# 011.net
KiCad netlist of a schematic drawn in EAGLE
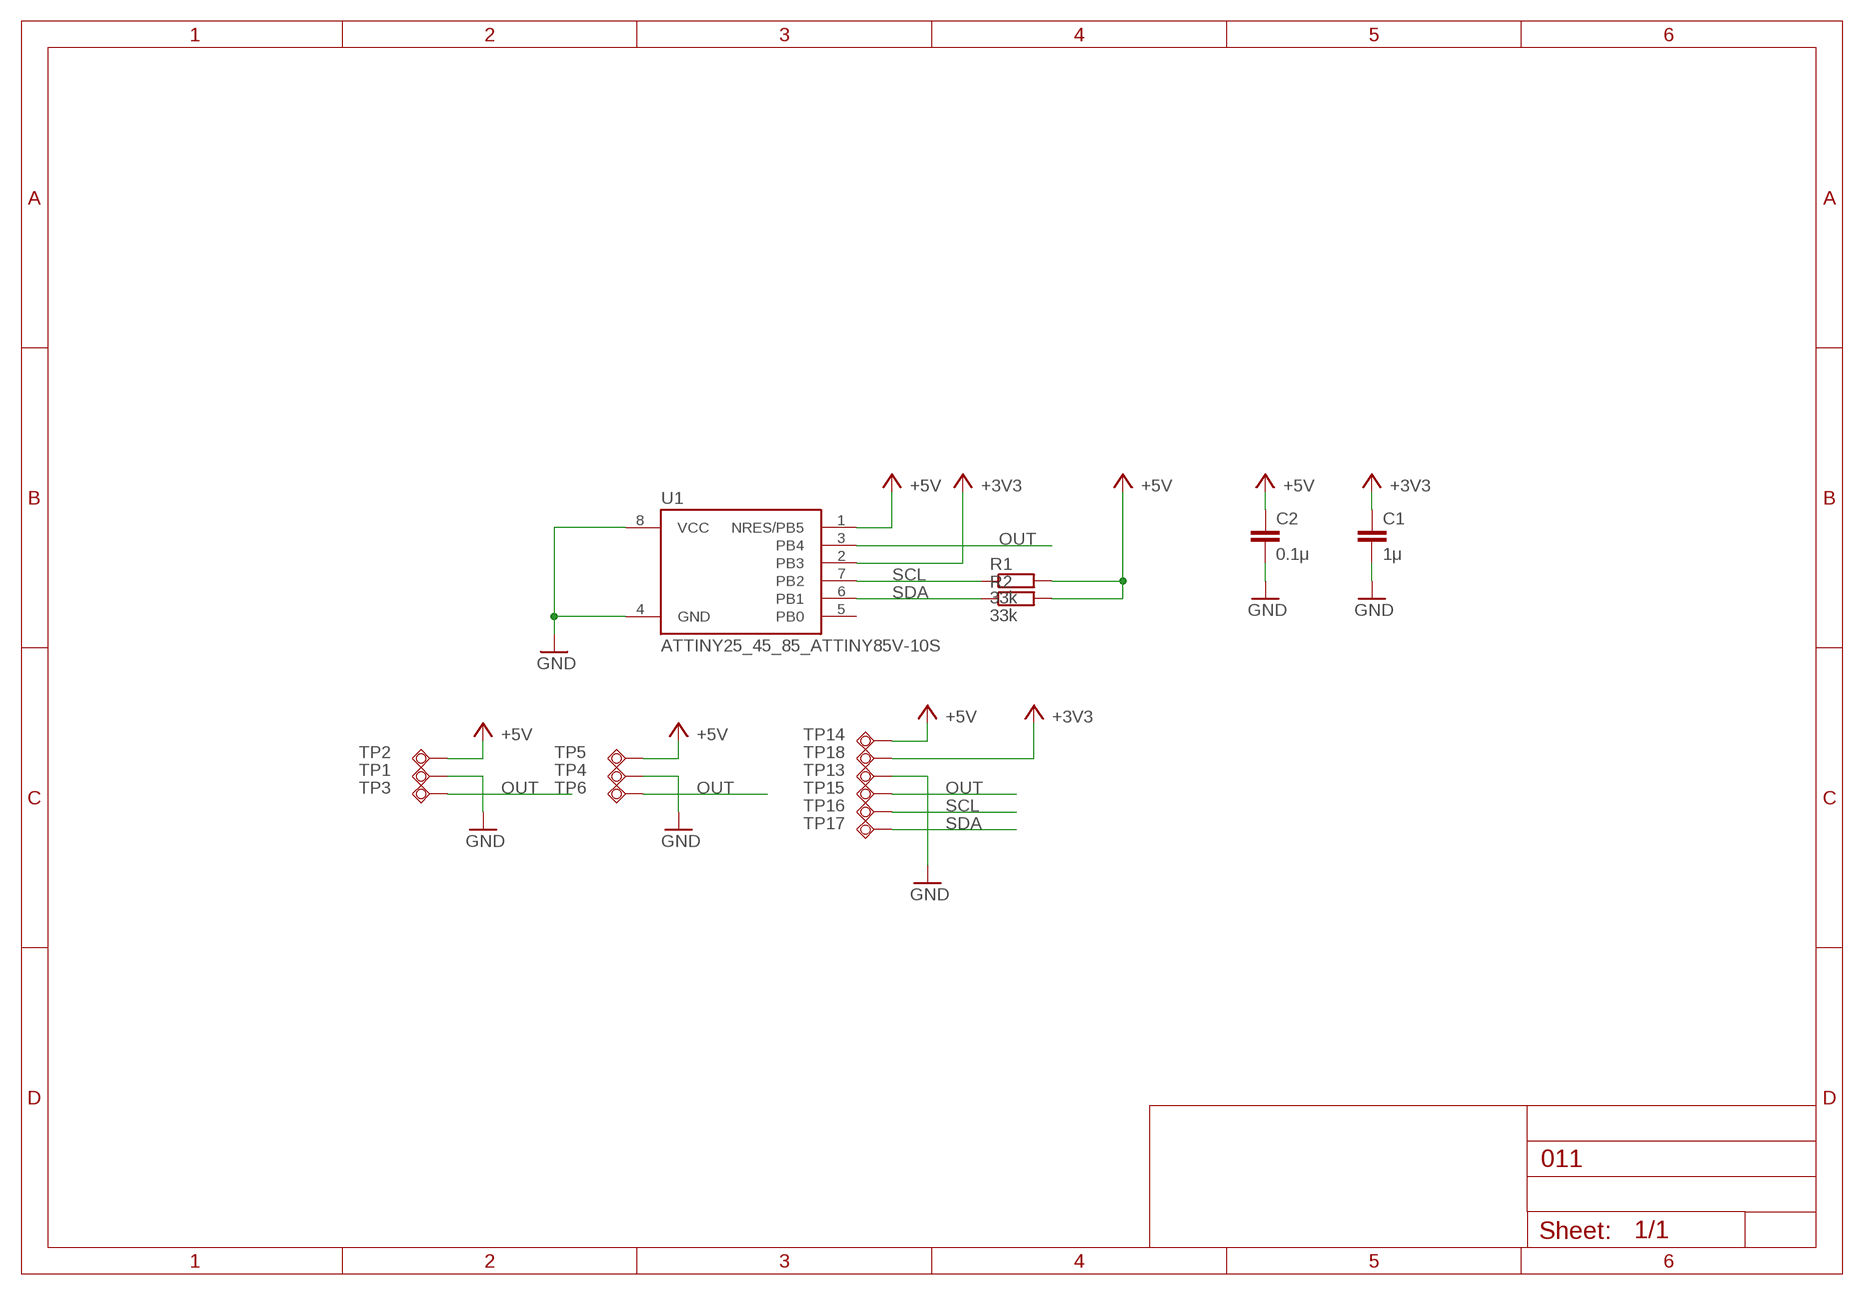
[diagram p0: schematic, sheet 1]

(export (version "E")
  (design (tool "Eeschema 10.0.6"))
  (components
    (comp (ref "C1")
      (value "1μ")
      (footprint "eagle-import:C0603")
      (libsource (lib "eagle-import") (part "C-EUC0603"))
    )
    (comp (ref "C2")
      (value "0.1μ")
      (footprint "eagle-import:C0603")
      (libsource (lib "eagle-import") (part "C-EUC0603"))
    )
    (comp (ref "R1")
      (value "33k")
      (footprint "eagle-import:R0603")
      (libsource (lib "eagle-import") (part "R-EU_R0603"))
    )
    (comp (ref "R2")
      (value "33k")
      (footprint "eagle-import:R0603")
      (libsource (lib "eagle-import") (part "R-EU_R0603"))
    )
    (comp (ref "TP1")
      (value "TPSQTP11R")
      (footprint "eagle-import:TP11R")
      (libsource (lib "eagle-import") (part "TPSQTP11R"))
    )
    (comp (ref "TP2")
      (value "TPSQTP11SQ")
      (footprint "eagle-import:TP11SQ")
      (libsource (lib "eagle-import") (part "TPSQTP11SQ"))
    )
    (comp (ref "TP3")
      (value "TPSQTP11R")
      (footprint "eagle-import:TP11R")
      (libsource (lib "eagle-import") (part "TPSQTP11R"))
    )
    (comp (ref "TP4")
      (value "TPSQTP11R")
      (footprint "eagle-import:TP11R")
      (libsource (lib "eagle-import") (part "TPSQTP11R"))
    )
    (comp (ref "TP5")
      (value "TPSQTP11SQ")
      (footprint "eagle-import:TP11SQ")
      (libsource (lib "eagle-import") (part "TPSQTP11SQ"))
    )
    (comp (ref "TP6")
      (value "TPSQTP11R")
      (footprint "eagle-import:TP11R")
      (libsource (lib "eagle-import") (part "TPSQTP11R"))
    )
    (comp (ref "TP13")
      (value "TPSQTP11R")
      (footprint "eagle-import:TP11R")
      (libsource (lib "eagle-import") (part "TPSQTP11R"))
    )
    (comp (ref "TP14")
      (value "TPSQTP11SQ")
      (footprint "eagle-import:TP11SQ")
      (libsource (lib "eagle-import") (part "TPSQTP11SQ"))
    )
    (comp (ref "TP15")
      (value "TPSQTP11R")
      (footprint "eagle-import:TP11R")
      (libsource (lib "eagle-import") (part "TPSQTP11R"))
    )
    (comp (ref "TP16")
      (value "TPSQTP11R")
      (footprint "eagle-import:TP11R")
      (libsource (lib "eagle-import") (part "TPSQTP11R"))
    )
    (comp (ref "TP17")
      (value "TPSQTP11R")
      (footprint "eagle-import:TP11R")
      (libsource (lib "eagle-import") (part "TPSQTP11R"))
    )
    (comp (ref "TP18")
      (value "TPSQTP11R")
      (footprint "eagle-import:TP11R")
      (libsource (lib "eagle-import") (part "TPSQTP11R"))
    )
    (comp (ref "U1")
      (value "ATTINY25_45_85_ATTINY85V-10S")
      (footprint "eagle-import:ATTINY25_45_85_SOIC8_EIAJ_208MIL")
      (libsource (lib "eagle-import") (part "ATTINY25_45_85_ATTINY85SV-10"))
    )
  )
  (nets
    (net (code "1") (name "+3V3") (class "Default")
      (node (ref "C1") (pin "1") (pinfunction "1_1") (pintype "passive"))
      (node (ref "TP18") (pin "TP") (pinfunction "TP_TP") (pintype "input"))
      (node (ref "U1") (pin "2") (pinfunction "PB3_2") (pintype "bidirectional"))
    )
    (net (code "2") (name "+5V") (class "Default")
      (node (ref "C2") (pin "1") (pinfunction "1_1") (pintype "passive"))
      (node (ref "R1") (pin "2") (pinfunction "2_2") (pintype "passive"))
      (node (ref "R2") (pin "2") (pinfunction "2_2") (pintype "passive"))
      (node (ref "TP14") (pin "TP") (pinfunction "TP_TP") (pintype "input"))
      (node (ref "TP2") (pin "TP") (pinfunction "TP_TP") (pintype "input"))
      (node (ref "TP5") (pin "TP") (pinfunction "TP_TP") (pintype "input"))
      (node (ref "U1") (pin "1") (pinfunction "NRES/PB5_1") (pintype "bidirectional"))
    )
    (net (code "3") (name "/OUT") (class "Default")
      (node (ref "TP15") (pin "TP") (pinfunction "TP_TP") (pintype "input"))
      (node (ref "TP3") (pin "TP") (pinfunction "TP_TP") (pintype "input"))
      (node (ref "TP6") (pin "TP") (pinfunction "TP_TP") (pintype "input"))
      (node (ref "U1") (pin "3") (pinfunction "PB4_3") (pintype "bidirectional"))
    )
    (net (code "4") (name "/SCL") (class "Default")
      (node (ref "R1") (pin "1") (pinfunction "1_1") (pintype "passive"))
      (node (ref "TP16") (pin "TP") (pinfunction "TP_TP") (pintype "input"))
      (node (ref "U1") (pin "7") (pinfunction "PB2_7") (pintype "bidirectional"))
    )
    (net (code "5") (name "/SDA") (class "Default")
      (node (ref "R2") (pin "1") (pinfunction "1_1") (pintype "passive"))
      (node (ref "TP17") (pin "TP") (pinfunction "TP_TP") (pintype "input"))
      (node (ref "U1") (pin "6") (pinfunction "PB1_6") (pintype "bidirectional"))
    )
    (net (code "6") (name "GND") (class "Default")
      (node (ref "C1") (pin "2") (pinfunction "2_2") (pintype "passive"))
      (node (ref "C2") (pin "2") (pinfunction "2_2") (pintype "passive"))
      (node (ref "TP1") (pin "TP") (pinfunction "TP_TP") (pintype "input"))
      (node (ref "TP13") (pin "TP") (pinfunction "TP_TP") (pintype "input"))
      (node (ref "TP4") (pin "TP") (pinfunction "TP_TP") (pintype "input"))
      (node (ref "U1") (pin "4") (pinfunction "GND_4") (pintype "power_in"))
      (node (ref "U1") (pin "8") (pinfunction "VCC_8") (pintype "power_in"))
    )
    (net (code "7") (name "unconnected-(U1-PB0-Pad5)") (class "Default")
      (node (ref "U1") (pin "5") (pinfunction "PB0_5") (pintype "bidirectional"))
    )
  )
)
